# ESP32-SCHEMATIC.net
KiCad netlist of a schematic drawn in Altium Designer
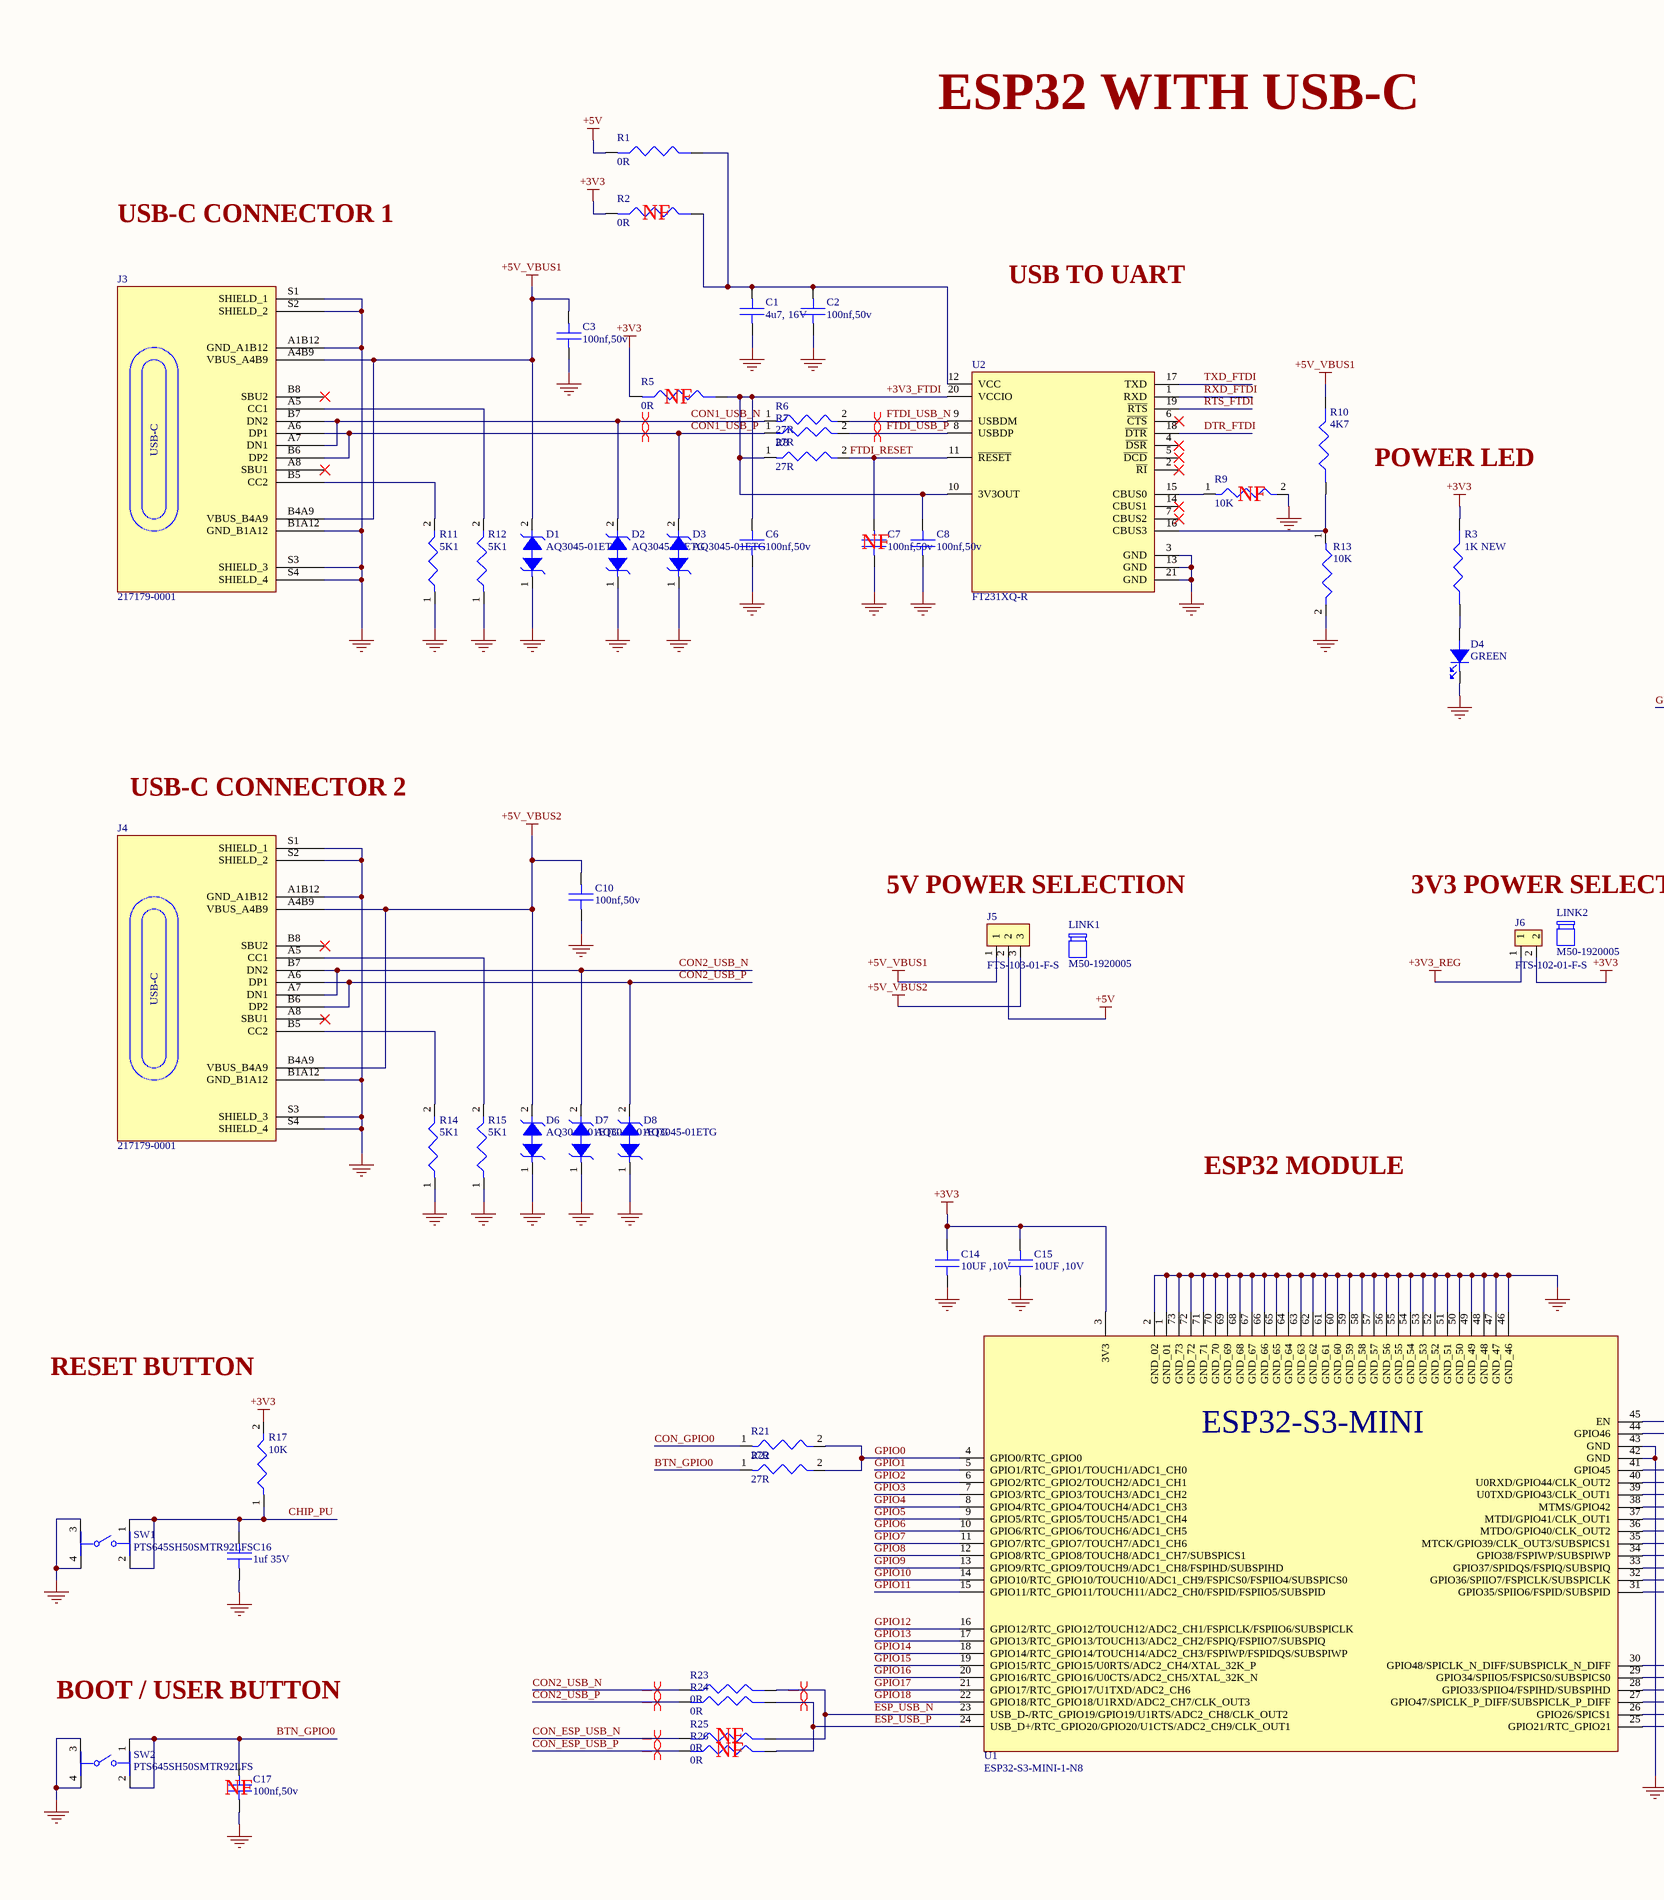
[diagram p0: ESP32-SCHEMATIC.SchDoc, left]
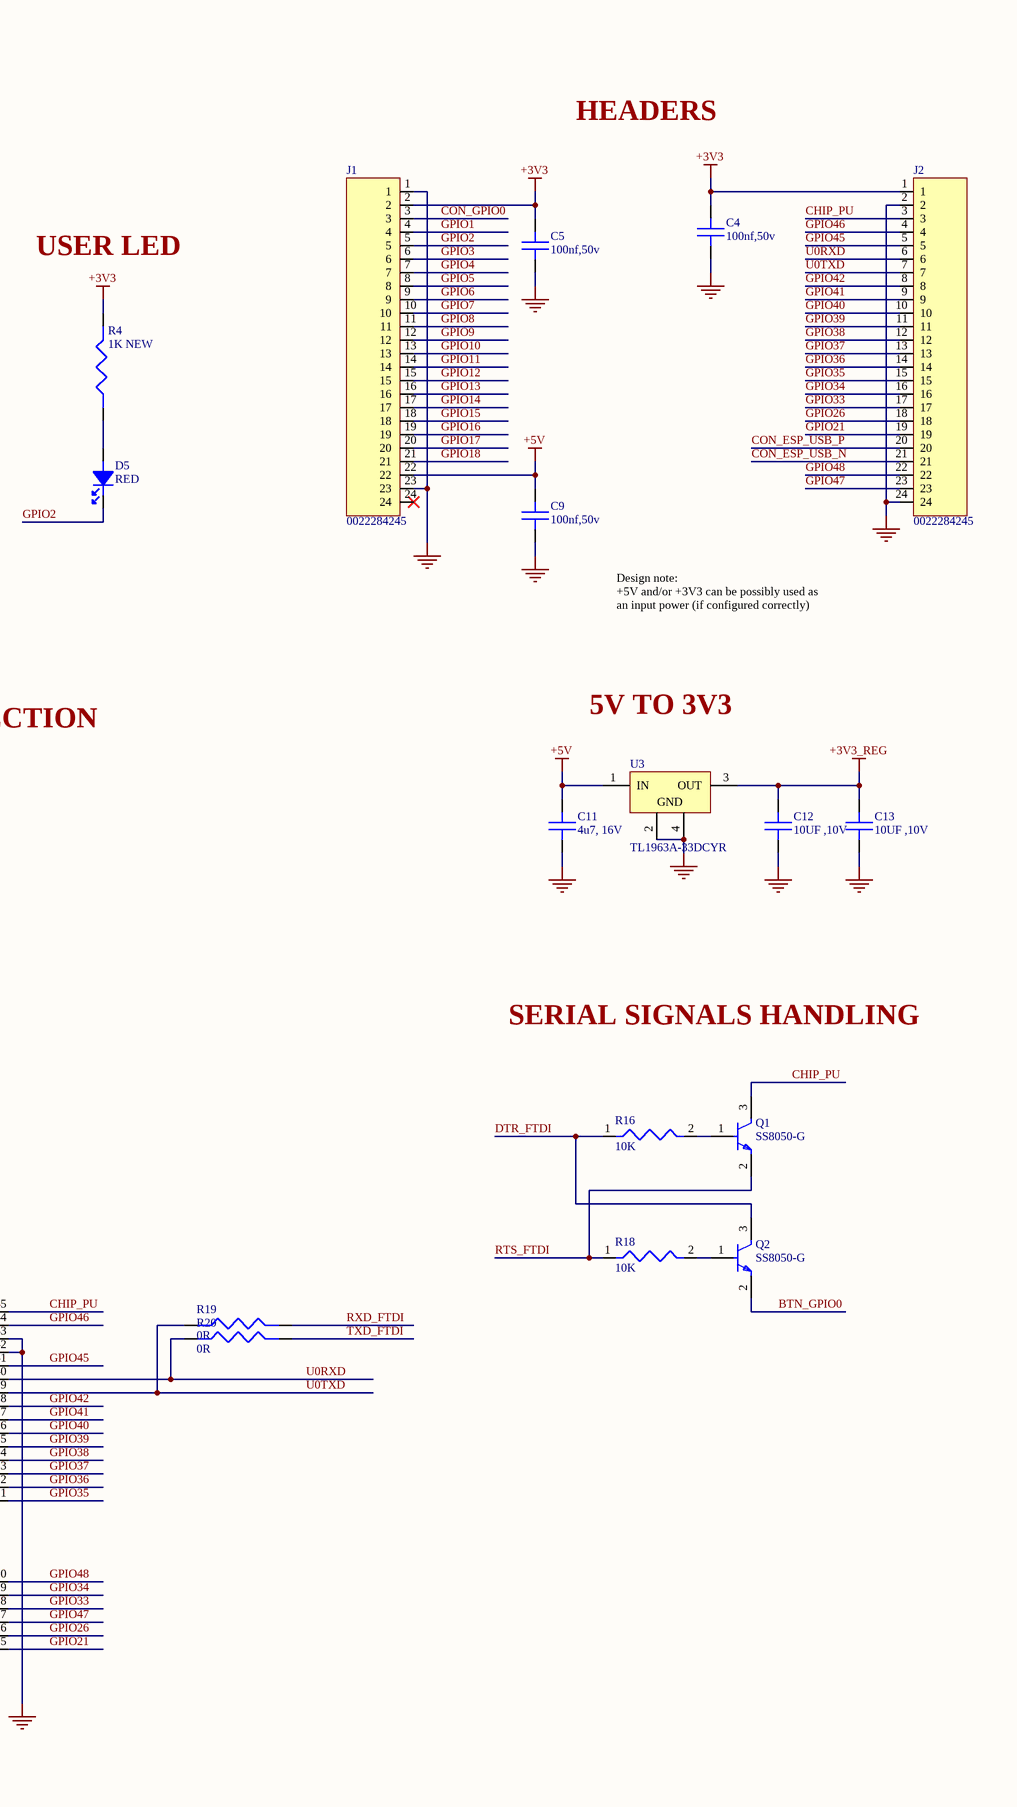
[diagram p1: ESP32-SCHEMATIC.SchDoc, right]

(export (version "E")
  (design (tool "Eeschema 10.0.6"))
  (components
    (comp (ref "C1")
      (value "4u7, 16V")
      (footprint "CAPC1005X55N")
      (description "16V 4.7uF X5R ±20% 0402 Multilayer Ceramic Capacitors MLCC - SMD/SMT ROHS")
      (fields
        (field (name "MANUFACTURER") "Samsung Electro-Mechanics")
        (field (name "MANUFACTURER PART NUMBER") "CL05A475MO5NUNC")
      )
      (libsource (lib "Schlib1") (part "CL05A475MO5NUNC"))
    )
    (comp (ref "C2")
      (value "100nf,50v")
      (footprint "CAPC1005X55N")
      (description "50V 100nF X7R ±10% 0402 Multilayer Ceramic Capacitors MLCC - SMD/SMT ROHS")
      (fields
        (field (name "MANUFACTURER") "Samsung Electro-Mechanics")
        (field (name "MANUFACTURER PART NUMBER") "CL05B104KB54PNC")
      )
      (libsource (lib "Schlib1") (part "CL05B104KB54PNC"))
    )
    (comp (ref "C3")
      (value "100nf,50v")
      (footprint "CAPC1005X55N")
      (description "50V 100nF X7R ±10% 0402 Multilayer Ceramic Capacitors MLCC - SMD/SMT ROHS")
      (fields
        (field (name "MANUFACTURER") "Samsung Electro-Mechanics")
        (field (name "MANUFACTURER PART NUMBER") "CL05B104KB54PNC")
      )
      (libsource (lib "Schlib1") (part "CL05B104KB54PNC"))
    )
    (comp (ref "C4")
      (value "100nf,50v")
      (footprint "CAPC1005X55N")
      (description "50V 100nF X7R ±10% 0402 Multilayer Ceramic Capacitors MLCC - SMD/SMT ROHS")
      (fields
        (field (name "MANUFACTURER") "Samsung Electro-Mechanics")
        (field (name "MANUFACTURER PART NUMBER") "CL05B104KB54PNC")
      )
      (libsource (lib "Schlib1") (part "CL05B104KB54PNC"))
    )
    (comp (ref "C5")
      (value "100nf,50v")
      (footprint "CAPC1005X55N")
      (description "50V 100nF X7R ±10% 0402 Multilayer Ceramic Capacitors MLCC - SMD/SMT ROHS")
      (fields
        (field (name "MANUFACTURER") "Samsung Electro-Mechanics")
        (field (name "MANUFACTURER PART NUMBER") "CL05B104KB54PNC")
      )
      (libsource (lib "Schlib1") (part "CL05B104KB54PNC"))
    )
    (comp (ref "C6")
      (value "100nf,50v")
      (footprint "CAPC1005X55N")
      (description "50V 100nF X7R ±10% 0402 Multilayer Ceramic Capacitors MLCC - SMD/SMT ROHS")
      (fields
        (field (name "MANUFACTURER") "Samsung Electro-Mechanics")
        (field (name "MANUFACTURER PART NUMBER") "CL05B104KB54PNC")
      )
      (libsource (lib "Schlib1") (part "CL05B104KB54PNC"))
    )
    (comp (ref "C7")
      (value "100nf,50v")
      (footprint "CAPC1005X55N")
      (description "50V 100nF X7R ±10% 0402 Multilayer Ceramic Capacitors MLCC - SMD/SMT ROHS")
      (fields
        (field (name "MANUFACTURER") "Samsung Electro-Mechanics")
        (field (name "MANUFACTURER PART NUMBER") "CL05B104KB54PNC")
      )
      (libsource (lib "Schlib1") (part "CL05B104KB54PNC"))
    )
    (comp (ref "C8")
      (value "100nf,50v")
      (footprint "CAPC1005X55N")
      (description "50V 100nF X7R ±10% 0402 Multilayer Ceramic Capacitors MLCC - SMD/SMT ROHS")
      (fields
        (field (name "MANUFACTURER") "Samsung Electro-Mechanics")
        (field (name "MANUFACTURER PART NUMBER") "CL05B104KB54PNC")
      )
      (libsource (lib "Schlib1") (part "CL05B104KB54PNC"))
    )
    (comp (ref "C9")
      (value "100nf,50v")
      (footprint "CAPC1005X55N")
      (description "50V 100nF X7R ±10% 0402 Multilayer Ceramic Capacitors MLCC - SMD/SMT ROHS")
      (fields
        (field (name "MANUFACTURER") "Samsung Electro-Mechanics")
        (field (name "MANUFACTURER PART NUMBER") "CL05B104KB54PNC")
      )
      (libsource (lib "Schlib1") (part "CL05B104KB54PNC"))
    )
    (comp (ref "C10")
      (value "100nf,50v")
      (footprint "CAPC1005X55N")
      (description "50V 100nF X7R ±10% 0402 Multilayer Ceramic Capacitors MLCC - SMD/SMT ROHS")
      (fields
        (field (name "MANUFACTURER") "Samsung Electro-Mechanics")
        (field (name "MANUFACTURER PART NUMBER") "CL05B104KB54PNC")
      )
      (libsource (lib "Schlib1") (part "CL05B104KB54PNC"))
    )
    (comp (ref "C11")
      (value "4u7, 16V")
      (footprint "CAPC1005X55N")
      (description "16V 4.7uF X5R ±20% 0402 Multilayer Ceramic Capacitors MLCC - SMD/SMT ROHS")
      (fields
        (field (name "MANUFACTURER") "Samsung Electro-Mechanics")
        (field (name "MANUFACTURER PART NUMBER") "CL05A475MO5NUNC")
      )
      (libsource (lib "Schlib1") (part "CL05A475MO5NUNC"))
    )
    (comp (ref "C12")
      (value "10UF ,10V")
      (footprint "CAPC1005X55N")
      (fields
        (field (name "MANUFACTURER") "Samsung Electro-Mechanics")
        (field (name "MANUFACTURER PART NUMBER") "CL05A106MP8NUB8")
        (field (name "TOLERANCE") "20%")
      )
      (libsource (lib "Schlib1") (part "CL05A106MP8NUB8"))
    )
    (comp (ref "C13")
      (value "10UF ,10V")
      (footprint "CAPC1005X55N")
      (fields
        (field (name "MANUFACTURER") "Samsung Electro-Mechanics")
        (field (name "MANUFACTURER PART NUMBER") "CL05A106MP8NUB8")
        (field (name "TOLERANCE") "20%")
      )
      (libsource (lib "Schlib1") (part "CL05A106MP8NUB8"))
    )
    (comp (ref "C14")
      (value "10UF ,10V")
      (footprint "CAPC1005X55N")
      (fields
        (field (name "MANUFACTURER") "Samsung Electro-Mechanics")
        (field (name "MANUFACTURER PART NUMBER") "CL05A106MP8NUB8")
        (field (name "TOLERANCE") "20%")
      )
      (libsource (lib "Schlib1") (part "CL05A106MP8NUB8"))
    )
    (comp (ref "C15")
      (value "10UF ,10V")
      (footprint "CAPC1005X55N")
      (fields
        (field (name "MANUFACTURER") "Samsung Electro-Mechanics")
        (field (name "MANUFACTURER PART NUMBER") "CL05A106MP8NUB8")
        (field (name "TOLERANCE") "20%")
      )
      (libsource (lib "Schlib1") (part "CL05A106MP8NUB8"))
    )
    (comp (ref "C16")
      (value "1uf 35V")
      (footprint "CAPC1005X55N")
      (description "35V 1uF X5R ±10% 0402 Multilayer Ceramic Capacitors MLCC - SMD/SMT ROHS")
      (fields
        (field (name "MANUFACTURER") "Samsung Electro-Mechanics")
        (field (name "MANUFACTURER PART NUMBER") "CL05A105KL5NRNC")
      )
      (libsource (lib "Schlib1") (part "CL05A105KL5NRNC"))
    )
    (comp (ref "C17")
      (value "100nf,50v")
      (footprint "CAPC1005X55N")
      (description "50V 100nF X7R ±10% 0402 Multilayer Ceramic Capacitors MLCC - SMD/SMT ROHS")
      (fields
        (field (name "MANUFACTURER") "Samsung Electro-Mechanics")
        (field (name "MANUFACTURER PART NUMBER") "CL05B104KB54PNC")
      )
      (libsource (lib "Schlib1") (part "CL05B104KB54PNC"))
    )
    (comp (ref "D1")
      (value "AQ3045-01ETG")
      (footprint "SOD882")
      (description "Bi 30Kv 5V 0.35Pf Automotve Tvs Sod882/ Tr Rohs Compliant: Yes ¦Littelfuse AQ3045-01ETG")
      (fields (field (name "MANUFACTURER") "Littelfuse"))
      (libsource (lib "Schlib1") (part "AQ3045-01ETG"))
    )
    (comp (ref "D2")
      (value "AQ3045-01ETG")
      (footprint "SOD882")
      (description "Bi 30Kv 5V 0.35Pf Automotve Tvs Sod882/ Tr Rohs Compliant: Yes ¦Littelfuse AQ3045-01ETG")
      (fields (field (name "MANUFACTURER") "Littelfuse"))
      (libsource (lib "Schlib1") (part "AQ3045-01ETG"))
    )
    (comp (ref "D3")
      (value "AQ3045-01ETG")
      (footprint "SOD882")
      (description "Bi 30Kv 5V 0.35Pf Automotve Tvs Sod882/ Tr Rohs Compliant: Yes ¦Littelfuse AQ3045-01ETG")
      (fields (field (name "MANUFACTURER") "Littelfuse"))
      (libsource (lib "Schlib1") (part "AQ3045-01ETG"))
    )
    (comp (ref "D4")
      (value "GREEN")
      (footprint "LED0402G")
      (description "LED Uni-Color Green 574nm 2-Pin Chip 0402(1006Metric) T/R")
      (fields
        (field (name "MANUFACTURER") "Vishay")
        (field (name "MANUFACTURER PART NUMBER") "VLMG1500-GS08")
      )
      (libsource (lib "Schlib1") (part "VLMG1500-GS08"))
    )
    (comp (ref "D5")
      (value "RED")
      (footprint "LED0402R")
      (description "LED Uni-Color Super Red 639nm 2-Pin Chip 0402(1006Metric) T/R")
      (fields
        (field (name "MANUFACTURER") "Vishay")
        (field (name "MANUFACTURER PART NUMBER") "VLMS1500-GS08")
      )
      (libsource (lib "Schlib1") (part "VLMS1500-GS08"))
    )
    (comp (ref "D6")
      (value "AQ3045-01ETG")
      (footprint "SOD882")
      (description "Bi 30Kv 5V 0.35Pf Automotve Tvs Sod882/ Tr Rohs Compliant: Yes ¦Littelfuse AQ3045-01ETG")
      (fields (field (name "MANUFACTURER") "Littelfuse"))
      (libsource (lib "Schlib1") (part "AQ3045-01ETG"))
    )
    (comp (ref "D7")
      (value "AQ3045-01ETG")
      (footprint "SOD882")
      (description "Bi 30Kv 5V 0.35Pf Automotve Tvs Sod882/ Tr Rohs Compliant: Yes ¦Littelfuse AQ3045-01ETG")
      (fields (field (name "MANUFACTURER") "Littelfuse"))
      (libsource (lib "Schlib1") (part "AQ3045-01ETG"))
    )
    (comp (ref "D8")
      (value "AQ3045-01ETG")
      (footprint "SOD882")
      (description "Bi 30Kv 5V 0.35Pf Automotve Tvs Sod882/ Tr Rohs Compliant: Yes ¦Littelfuse AQ3045-01ETG")
      (fields (field (name "MANUFACTURER") "Littelfuse"))
      (libsource (lib "Schlib1") (part "AQ3045-01ETG"))
    )
    (comp (ref "J1")
      (value "0022284245")
      (footprint "HDR_1X24_2.54MM")
      (description "Conn Unshrouded Header HDR 24 POS 2.54mm Solder ST Thru-Hole KK® Bag")
      (fields (field (name "MANUFACTURER") "Molex") (field (name "MANUFACTURER PART NUMBER") "22-28-4245"))
      (libsource (lib "") (part "22-28-4245_1"))
    )
    (comp (ref "J2")
      (value "0022284245")
      (footprint "HDR_1X24_2.54MM")
      (description "Conn Unshrouded Header HDR 24 POS 2.54mm Solder ST Thru-Hole KK® Bag")
      (fields (field (name "MANUFACTURER") "Molex") (field (name "MANUFACTURER PART NUMBER") "22-28-4245"))
      (libsource (lib "Schlib1") (part "22-28-4245"))
    )
    (comp (ref "J3")
      (value "217179-0001")
      (footprint "FP-2171790001-MFG")
      (description "USB Connector, USB Type C, USB 2.0, Receptacle, 16 Ways, Surface Mount, Through Hole Mount")
      (fields (field (name "MANUFACTURER") "Molex"))
      (libsource (lib "Schlib1") (part "217179-0001"))
    )
    (comp (ref "J4")
      (value "217179-0001")
      (footprint "FP-2171790001-MFG")
      (description "USB Connector, USB Type C, USB 2.0, Receptacle, 16 Ways, Surface Mount, Through Hole Mount")
      (fields (field (name "MANUFACTURER") "Molex"))
      (libsource (lib "Schlib1") (part "217179-0001"))
    )
    (comp (ref "J5")
      (value "FTS-103-01-F-S")
      (footprint "HDR_1X3_1.27MM")
      (description "Pin Header, Wire-to-Board, 1.27 mm, 1 Rows, 3 Contacts, Through Hole, FTS")
      (fields (field (name "MANUFACTURER") "Samtec"))
      (libsource (lib "Schlib1") (part "FTS-103-01-F-S"))
    )
    (comp (ref "J6")
      (value "FTS-102-01-F-S")
      (footprint "HDR_1X2_1.27MM")
      (description "Pin Header, Board-to-Board, 1.27 mm, 1 Rows, 2 Contacts, Through Hole Straight, FTS Series")
      (fields (field (name "MANUFACTURER") "Samtec"))
      (libsource (lib "Schlib1") (part "FTS-102-01-F-S"))
    )
    (comp (ref "LINK1")
      (value "M50-1920005")
      (description "1.27mm (0.05) Pitch Closed Top Jumper Socket, red, gold\"")
      (fields (field (name "MANUFACTURER") "Harwin"))
      (libsource (lib "Schlib1") (part "M50-1920005"))
    )
    (comp (ref "LINK2")
      (value "M50-1920005")
      (description "1.27mm (0.05) Pitch Closed Top Jumper Socket, red, gold\"")
      (fields (field (name "MANUFACTURER") "Harwin"))
      (libsource (lib "Schlib1") (part "M50-1920005"))
    )
    (comp (ref "Q1")
      (value "SS8050-G")
      (footprint "FP-SS8050-G-IPC_B")
      (description "Trans Gp Bjt NPN 25V 1.5A 300MW 3-PIN SOT-23 T/r")
      (fields (field (name "MANUFACTURER") "Comchip"))
      (libsource (lib "Schlib1") (part "SS8050-G"))
    )
    (comp (ref "Q2")
      (value "SS8050-G")
      (footprint "FP-SS8050-G-IPC_B")
      (description "Trans Gp Bjt NPN 25V 1.5A 300MW 3-PIN SOT-23 T/r")
      (fields (field (name "MANUFACTURER") "Comchip"))
      (libsource (lib "Schlib1") (part "SS8050-G"))
    )
    (comp (ref "R1")
      (value "0R")
      (footprint "RESC1005X37N")
      (description "GENERAL PURPOSE CHIP RESISTOR Metal Glaze/thick Film, 0.0625W, 0ohm, Surface Mount, 0402")
      (fields
        (field (name "MANUFACTURER") "Yageo Group")
        (field (name "MANUFACTURER PART NUMBER") "RC0402JR-070RL")
      )
      (libsource (lib "Schlib1") (part "RC0402JR-070RL"))
    )
    (comp (ref "R2")
      (value "0R")
      (footprint "RESC1005X37N")
      (description "GENERAL PURPOSE CHIP RESISTOR Metal Glaze/thick Film, 0.0625W, 0ohm, Surface Mount, 0402")
      (fields
        (field (name "MANUFACTURER") "Yageo Group")
        (field (name "MANUFACTURER PART NUMBER") "RC0402JR-070RL")
      )
      (libsource (lib "Schlib1") (part "RC0402JR-070RL"))
    )
    (comp (ref "R3")
      (value "1K NEW")
      (footprint "RESC1005X37N")
      (description "Resistor, thick film, SMD 0402 (1005), 1 kΩ, 0.063 W, ±1 %, RC0402FR-071KL")
      (fields
        (field (name "MANUFACTURER") "Yageo Group")
        (field (name "MANUFACTURER PART NUMBER") "RC0402FR-071KL")
      )
      (libsource (lib "Schlib1") (part "RC0402FR-071KL"))
    )
    (comp (ref "R4")
      (value "1K NEW")
      (footprint "RESC1005X37N")
      (description "Resistor, thick film, SMD 0402 (1005), 1 kΩ, 0.063 W, ±1 %, RC0402FR-071KL")
      (fields
        (field (name "MANUFACTURER") "Yageo Group")
        (field (name "MANUFACTURER PART NUMBER") "RC0402FR-071KL")
      )
      (libsource (lib "Schlib1") (part "RC0402FR-071KL"))
    )
    (comp (ref "R5")
      (value "0R")
      (footprint "RESC1005X37N")
      (description "GENERAL PURPOSE CHIP RESISTOR Metal Glaze/thick Film, 0.0625W, 0ohm, Surface Mount, 0402")
      (fields
        (field (name "MANUFACTURER") "Yageo Group")
        (field (name "MANUFACTURER PART NUMBER") "RC0402JR-070RL")
      )
      (libsource (lib "Schlib1") (part "RC0402JR-070RL"))
    )
    (comp (ref "R6")
      (value "27R")
      (footprint "RESC1005X37N")
      (description "62.5mW Thick Film Resistors 50V ±100ppm/℃ ±1% 27Ω 0402 Chip Resistor - Surface Mount ROHS")
      (fields
        (field (name "MANUFACTURER") "Yageo Group")
        (field (name "MANUFACTURER PART NUMBER") "RC0402FR-0727RL")
      )
      (libsource (lib "Schlib1") (part "RC0402FR-0727RL"))
    )
    (comp (ref "R7")
      (value "27R")
      (footprint "RESC1005X37N")
      (description "62.5mW Thick Film Resistors 50V ±100ppm/℃ ±1% 27Ω 0402 Chip Resistor - Surface Mount ROHS")
      (fields
        (field (name "MANUFACTURER") "Yageo Group")
        (field (name "MANUFACTURER PART NUMBER") "RC0402FR-0727RL")
      )
      (libsource (lib "Schlib1") (part "RC0402FR-0727RL"))
    )
    (comp (ref "R8")
      (value "27R")
      (footprint "RESC1005X37N")
      (description "62.5mW Thick Film Resistors 50V ±100ppm/℃ ±1% 27Ω 0402 Chip Resistor - Surface Mount ROHS")
      (fields
        (field (name "MANUFACTURER") "Yageo Group")
        (field (name "MANUFACTURER PART NUMBER") "RC0402FR-0727RL")
      )
      (libsource (lib "Schlib1") (part "RC0402FR-0727RL"))
    )
    (comp (ref "R9")
      (value "10K")
      (footprint "RESC1005X37N")
      (description "62.5mW Thick Film Resistors 50V ±100ppm/℃ ±1% 10kΩ 0402 Chip Resistor - Surface Mount ROHS")
      (fields
        (field (name "MANUFACTURER") "Yageo Group")
        (field (name "MANUFACTURER PART NUMBER") "SR0402FR-0710KL")
      )
      (libsource (lib "Schlib1") (part "SR0402FR-0710KL"))
    )
    (comp (ref "R10")
      (value "4K7")
      (footprint "RESC1005X37N")
      (description "Res General Purpose Thick Film 0402 4.7K Ohm 1% 1/16W ±100ppm/°C Molded SMD Paper T/R")
      (fields
        (field (name "MANUFACTURER") "Yageo Group")
        (field (name "MANUFACTURER PART NUMBER") "RC0402FR-074K7L")
      )
      (libsource (lib "Schlib1") (part "RC0402FR-074K7L"))
    )
    (comp (ref "R11")
      (value "5K1")
      (footprint "RESC1005X37N")
      (description "62.5mW Thick Film Resistors 50V ±100ppm/℃ ±1% 5.1kΩ 0402 Chip Resistor - Surface Mount ROHS")
      (fields
        (field (name "MANUFACTURER") "Yageo Group")
        (field (name "MANUFACTURER PART NUMBER") "AC0402FR-075K1L")
      )
      (libsource (lib "Schlib1") (part "AC0402FR-075K1L"))
    )
    (comp (ref "R12")
      (value "5K1")
      (footprint "RESC1005X37N")
      (description "62.5mW Thick Film Resistors 50V ±100ppm/℃ ±1% 5.1kΩ 0402 Chip Resistor - Surface Mount ROHS")
      (fields
        (field (name "MANUFACTURER") "Yageo Group")
        (field (name "MANUFACTURER PART NUMBER") "AC0402FR-075K1L")
      )
      (libsource (lib "Schlib1") (part "AC0402FR-075K1L"))
    )
    (comp (ref "R13")
      (value "10K")
      (footprint "RESC1005X37N")
      (description "62.5mW Thick Film Resistors 50V ±100ppm/℃ ±1% 10kΩ 0402 Chip Resistor - Surface Mount ROHS")
      (fields
        (field (name "MANUFACTURER") "Yageo Group")
        (field (name "MANUFACTURER PART NUMBER") "SR0402FR-0710KL")
      )
      (libsource (lib "Schlib1") (part "SR0402FR-0710KL"))
    )
    (comp (ref "R14")
      (value "5K1")
      (footprint "RESC1005X37N")
      (description "62.5mW Thick Film Resistors 50V ±100ppm/℃ ±1% 5.1kΩ 0402 Chip Resistor - Surface Mount ROHS")
      (fields
        (field (name "MANUFACTURER") "Yageo Group")
        (field (name "MANUFACTURER PART NUMBER") "AC0402FR-075K1L")
      )
      (libsource (lib "Schlib1") (part "AC0402FR-075K1L"))
    )
    (comp (ref "R15")
      (value "5K1")
      (footprint "RESC1005X37N")
      (description "62.5mW Thick Film Resistors 50V ±100ppm/℃ ±1% 5.1kΩ 0402 Chip Resistor - Surface Mount ROHS")
      (fields
        (field (name "MANUFACTURER") "Yageo Group")
        (field (name "MANUFACTURER PART NUMBER") "AC0402FR-075K1L")
      )
      (libsource (lib "Schlib1") (part "AC0402FR-075K1L"))
    )
    (comp (ref "R16")
      (value "10K")
      (footprint "RESC1005X37N")
      (description "62.5mW Thick Film Resistors 50V ±100ppm/℃ ±1% 10kΩ 0402 Chip Resistor - Surface Mount ROHS")
      (fields
        (field (name "MANUFACTURER") "Yageo Group")
        (field (name "MANUFACTURER PART NUMBER") "SR0402FR-0710KL")
      )
      (libsource (lib "Schlib1") (part "SR0402FR-0710KL"))
    )
    (comp (ref "R17")
      (value "10K")
      (footprint "RESC1005X37N")
      (description "62.5mW Thick Film Resistors 50V ±100ppm/℃ ±1% 10kΩ 0402 Chip Resistor - Surface Mount ROHS")
      (fields
        (field (name "MANUFACTURER") "Yageo Group")
        (field (name "MANUFACTURER PART NUMBER") "SR0402FR-0710KL")
      )
      (libsource (lib "Schlib1") (part "SR0402FR-0710KL"))
    )
    (comp (ref "R18")
      (value "10K")
      (footprint "RESC1005X37N")
      (description "62.5mW Thick Film Resistors 50V ±100ppm/℃ ±1% 10kΩ 0402 Chip Resistor - Surface Mount ROHS")
      (fields
        (field (name "MANUFACTURER") "Yageo Group")
        (field (name "MANUFACTURER PART NUMBER") "SR0402FR-0710KL")
      )
      (libsource (lib "Schlib1") (part "SR0402FR-0710KL"))
    )
    (comp (ref "R19")
      (value "0R")
      (footprint "RESC1005X37N")
      (description "GENERAL PURPOSE CHIP RESISTOR Metal Glaze/thick Film, 0.0625W, 0ohm, Surface Mount, 0402")
      (fields
        (field (name "MANUFACTURER") "Yageo Group")
        (field (name "MANUFACTURER PART NUMBER") "RC0402JR-070RL")
      )
      (libsource (lib "Schlib1") (part "RC0402JR-070RL"))
    )
    (comp (ref "R20")
      (value "0R")
      (footprint "RESC1005X37N")
      (description "GENERAL PURPOSE CHIP RESISTOR Metal Glaze/thick Film, 0.0625W, 0ohm, Surface Mount, 0402")
      (fields
        (field (name "MANUFACTURER") "Yageo Group")
        (field (name "MANUFACTURER PART NUMBER") "RC0402JR-070RL")
      )
      (libsource (lib "Schlib1") (part "RC0402JR-070RL"))
    )
    (comp (ref "R21")
      (value "27R")
      (footprint "RESC1005X37N")
      (description "62.5mW Thick Film Resistors 50V ±100ppm/℃ ±1% 27Ω 0402 Chip Resistor - Surface Mount ROHS")
      (fields
        (field (name "MANUFACTURER") "Yageo Group")
        (field (name "MANUFACTURER PART NUMBER") "RC0402FR-0727RL")
      )
      (libsource (lib "Schlib1") (part "RC0402FR-0727RL"))
    )
    (comp (ref "R22")
      (value "27R")
      (footprint "RESC1005X37N")
      (description "62.5mW Thick Film Resistors 50V ±100ppm/℃ ±1% 27Ω 0402 Chip Resistor - Surface Mount ROHS")
      (fields
        (field (name "MANUFACTURER") "Yageo Group")
        (field (name "MANUFACTURER PART NUMBER") "RC0402FR-0727RL")
      )
      (libsource (lib "Schlib1") (part "RC0402FR-0727RL"))
    )
    (comp (ref "R23")
      (value "0R")
      (footprint "RESC1005X37N")
      (description "GENERAL PURPOSE CHIP RESISTOR Metal Glaze/thick Film, 0.0625W, 0ohm, Surface Mount, 0402")
      (fields
        (field (name "MANUFACTURER") "Yageo Group")
        (field (name "MANUFACTURER PART NUMBER") "RC0402JR-070RL")
      )
      (libsource (lib "Schlib1") (part "RC0402JR-070RL"))
    )
    (comp (ref "R24")
      (value "0R")
      (footprint "RESC1005X37N")
      (description "GENERAL PURPOSE CHIP RESISTOR Metal Glaze/thick Film, 0.0625W, 0ohm, Surface Mount, 0402")
      (fields
        (field (name "MANUFACTURER") "Yageo Group")
        (field (name "MANUFACTURER PART NUMBER") "RC0402JR-070RL")
      )
      (libsource (lib "Schlib1") (part "RC0402JR-070RL"))
    )
    (comp (ref "R25")
      (value "0R")
      (footprint "RESC1005X37N")
      (description "GENERAL PURPOSE CHIP RESISTOR Metal Glaze/thick Film, 0.0625W, 0ohm, Surface Mount, 0402")
      (fields
        (field (name "MANUFACTURER") "Yageo Group")
        (field (name "MANUFACTURER PART NUMBER") "RC0402JR-070RL")
      )
      (libsource (lib "Schlib1") (part "RC0402JR-070RL"))
    )
    (comp (ref "R26")
      (value "0R")
      (footprint "RESC1005X37N")
      (description "GENERAL PURPOSE CHIP RESISTOR Metal Glaze/thick Film, 0.0625W, 0ohm, Surface Mount, 0402")
      (fields
        (field (name "MANUFACTURER") "Yageo Group")
        (field (name "MANUFACTURER PART NUMBER") "RC0402JR-070RL")
      )
      (libsource (lib "Schlib1") (part "RC0402JR-070RL"))
    )
    (comp (ref "SW1")
      (value "PTS645SH50SMTR92LFS")
      (footprint "FP-PTS645SH50SMTR92LFS-MFG")
      (description "Switch Tactile N.O. SPST Round Button Gull Wing 0.05A 12VDC 100000Cycles 1.96N SMD T/R")
      (fields (field (name "MANUFACTURER") "C&K Components"))
      (libsource (lib "Schlib1") (part "PTS645SH50SMTR92LFS"))
    )
    (comp (ref "SW2")
      (value "PTS645SH50SMTR92LFS")
      (footprint "FP-PTS645SH50SMTR92LFS-MFG")
      (description "Switch Tactile N.O. SPST Round Button Gull Wing 0.05A 12VDC 100000Cycles 1.96N SMD T/R")
      (fields (field (name "MANUFACTURER") "C&K Components"))
      (libsource (lib "Schlib1") (part "PTS645SH50SMTR92LFS"))
    )
    (comp (ref "U1")
      (value "ESP32-S3-MINI-1-N8")
      (footprint "XCVR_ESP32-S3-MINI-1-N8")
      (description "SMD module, ESP32-S3FN8, 8 MB SPI flash, PCB antenna")
      (fields (field (name "MANUFACTURER") "Espressif Systems"))
      (libsource (lib "Schlib1") (part "ESP32-S3-MINI-1-N8"))
    )
    (comp (ref "U2")
      (value "FT231XQ-R")
      (footprint "FP-QFN-20-IPC_B")
      (description "Tape & Reel (TR) 2006 UART USB 2.0 interface controller 3.3V~5V 4mm 8mA 12Mbps")
      (fields (field (name "MANUFACTURER") "FTDI"))
      (libsource (lib "Schlib1") (part "FT231XQ-R"))
    )
    (comp (ref "U3")
      (value "TL1963A-33DCYR")
      (footprint "DCY0004A_N")
      (description "1.5-A, 20-V, low-dropout voltage regulator with reverse current & reverse voltage protection")
      (fields (field (name "MANUFACTURER") "Texas Instruments"))
      (libsource (lib "Schlib1") (part "TL1963A-33DCYR"))
    )
  )
  (nets
    (net (code "1") (name "+3V3") (class "Default")
      (node (ref "C14") (pin "2") (pinfunction "2_2") (pintype "passive"))
      (node (ref "C15") (pin "2") (pinfunction "2_2") (pintype "passive"))
      (node (ref "C4") (pin "2") (pinfunction "2_2") (pintype "passive"))
      (node (ref "C5") (pin "2") (pinfunction "2_2") (pintype "passive"))
      (node (ref "J1") (pin "2") (pinfunction "2_2") (pintype "passive"))
      (node (ref "J2") (pin "1") (pinfunction "1_1") (pintype "passive"))
      (node (ref "J6") (pin "2") (pinfunction "2_2") (pintype "passive"))
      (node (ref "R17") (pin "2") (pinfunction "2_2") (pintype "passive"))
      (node (ref "R2") (pin "1") (pinfunction "1_1") (pintype "passive"))
      (node (ref "R3") (pin "2") (pinfunction "2_2") (pintype "passive"))
      (node (ref "R4") (pin "2") (pinfunction "2_2") (pintype "passive"))
      (node (ref "R5") (pin "1") (pinfunction "1_1") (pintype "passive"))
      (node (ref "U1") (pin "3") (pinfunction "3V3_3") (pintype "passive"))
    )
    (net (code "2") (name "+3V3_REG") (class "Default")
      (node (ref "C12") (pin "2") (pinfunction "2_2") (pintype "passive"))
      (node (ref "C13") (pin "2") (pinfunction "2_2") (pintype "passive"))
      (node (ref "J6") (pin "1") (pinfunction "1_1") (pintype "passive"))
      (node (ref "U3") (pin "3") (pinfunction "OUT_3") (pintype "power_in"))
    )
    (net (code "3") (name "+5V") (class "Default")
      (node (ref "C11") (pin "2") (pinfunction "2_2") (pintype "passive"))
      (node (ref "C9") (pin "2") (pinfunction "2_2") (pintype "passive"))
      (node (ref "J1") (pin "22") (pinfunction "22_22") (pintype "passive"))
      (node (ref "J5") (pin "2") (pinfunction "2_2") (pintype "passive"))
      (node (ref "R1") (pin "1") (pinfunction "1_1") (pintype "passive"))
      (node (ref "U3") (pin "1") (pinfunction "IN_1") (pintype "power_in"))
    )
    (net (code "4") (name "+5V_VBUS1") (class "Default")
      (node (ref "C3") (pin "2") (pinfunction "2_2") (pintype "passive"))
      (node (ref "D1") (pin "2") (pinfunction "2_2") (pintype "passive"))
      (node (ref "J3") (pin "A4B9") (pinfunction "VBUS_A4B9_A4B9") (pintype "passive"))
      (node (ref "J3") (pin "B4A9") (pinfunction "VBUS_B4A9_B4A9") (pintype "passive"))
      (node (ref "J5") (pin "1") (pinfunction "1_1") (pintype "passive"))
      (node (ref "R10") (pin "2") (pinfunction "2_2") (pintype "passive"))
    )
    (net (code "5") (name "+5V_VBUS2") (class "Default")
      (node (ref "C10") (pin "2") (pinfunction "2_2") (pintype "passive"))
      (node (ref "D6") (pin "2") (pinfunction "2_2") (pintype "passive"))
      (node (ref "J4") (pin "A4B9") (pinfunction "VBUS_A4B9_A4B9") (pintype "passive"))
      (node (ref "J4") (pin "B4A9") (pinfunction "VBUS_B4A9_B4A9") (pintype "passive"))
      (node (ref "J5") (pin "3") (pinfunction "3_3") (pintype "passive"))
    )
    (net (code "6") (name "/+3V3_FTDI") (class "Default")
      (node (ref "C6") (pin "2") (pinfunction "2_2") (pintype "passive"))
      (node (ref "C8") (pin "2") (pinfunction "2_2") (pintype "passive"))
      (node (ref "R5") (pin "2") (pinfunction "2_2") (pintype "passive"))
      (node (ref "R8") (pin "1") (pinfunction "1_1") (pintype "passive"))
      (node (ref "U2") (pin "10") (pinfunction "3V3OUT_10") (pintype "passive"))
      (node (ref "U2") (pin "20") (pinfunction "VCCIO_20") (pintype "passive"))
    )
    (net (code "7") (name "/BTN_GPIO0") (class "Default")
      (node (ref "C17") (pin "2") (pinfunction "2_2") (pintype "passive"))
      (node (ref "Q2") (pin "2") (pinfunction "E_2") (pintype "passive"))
      (node (ref "R22") (pin "1") (pinfunction "1_1") (pintype "passive"))
      (node (ref "SW2") (pin "1") (pinfunction "1_1") (pintype "passive"))
      (node (ref "SW2") (pin "2") (pinfunction "2_2") (pintype "passive"))
    )
    (net (code "8") (name "/CHIP_PU") (class "Default")
      (node (ref "C16") (pin "2") (pinfunction "2_2") (pintype "passive"))
      (node (ref "J2") (pin "3") (pinfunction "3_3") (pintype "passive"))
      (node (ref "Q1") (pin "3") (pinfunction "C_3") (pintype "passive"))
      (node (ref "R17") (pin "1") (pinfunction "1_1") (pintype "passive"))
      (node (ref "SW1") (pin "1") (pinfunction "1_1") (pintype "passive"))
      (node (ref "SW1") (pin "2") (pinfunction "2_2") (pintype "passive"))
      (node (ref "U1") (pin "45") (pinfunction "EN_45") (pintype "passive"))
    )
    (net (code "9") (name "/CON1_USB_N") (class "Default")
      (node (ref "D2") (pin "2") (pinfunction "2_2") (pintype "passive"))
      (node (ref "J3") (pin "A7") (pinfunction "DN1_A7") (pintype "passive"))
      (node (ref "J3") (pin "B7") (pinfunction "DN2_B7") (pintype "passive"))
      (node (ref "R6") (pin "1") (pinfunction "1_1") (pintype "passive"))
    )
    (net (code "10") (name "/CON1_USB_P") (class "Default")
      (node (ref "D3") (pin "2") (pinfunction "2_2") (pintype "passive"))
      (node (ref "J3") (pin "A6") (pinfunction "DP1_A6") (pintype "passive"))
      (node (ref "J3") (pin "B6") (pinfunction "DP2_B6") (pintype "passive"))
      (node (ref "R7") (pin "1") (pinfunction "1_1") (pintype "passive"))
    )
    (net (code "11") (name "/CON2_USB_N") (class "Default")
      (node (ref "D7") (pin "2") (pinfunction "2_2") (pintype "passive"))
      (node (ref "J4") (pin "A7") (pinfunction "DN1_A7") (pintype "passive"))
      (node (ref "J4") (pin "B7") (pinfunction "DN2_B7") (pintype "passive"))
      (node (ref "R23") (pin "1") (pinfunction "1_1") (pintype "passive"))
    )
    (net (code "12") (name "/CON2_USB_P") (class "Default")
      (node (ref "D8") (pin "2") (pinfunction "2_2") (pintype "passive"))
      (node (ref "J4") (pin "A6") (pinfunction "DP1_A6") (pintype "passive"))
      (node (ref "J4") (pin "B6") (pinfunction "DP2_B6") (pintype "passive"))
      (node (ref "R24") (pin "1") (pinfunction "1_1") (pintype "passive"))
    )
    (net (code "13") (name "/CON_ESP_USB_N") (class "Default")
      (node (ref "J2") (pin "21") (pinfunction "21_21") (pintype "passive"))
      (node (ref "R25") (pin "1") (pinfunction "1_1") (pintype "passive"))
    )
    (net (code "14") (name "/CON_ESP_USB_P") (class "Default")
      (node (ref "J2") (pin "20") (pinfunction "20_20") (pintype "passive"))
      (node (ref "R26") (pin "1") (pinfunction "1_1") (pintype "passive"))
    )
    (net (code "15") (name "/CON_GPIO0") (class "Default")
      (node (ref "J1") (pin "3") (pinfunction "3_3") (pintype "passive"))
      (node (ref "R21") (pin "1") (pinfunction "1_1") (pintype "passive"))
    )
    (net (code "16") (name "/DTR_FTDI") (class "Default")
      (node (ref "Q2") (pin "3") (pinfunction "C_3") (pintype "passive"))
      (node (ref "R16") (pin "1") (pinfunction "1_1") (pintype "passive"))
      (node (ref "U2") (pin "18") (pinfunction "~{DTR}_18") (pintype "passive"))
    )
    (net (code "17") (name "/ESP_USB_N") (class "Default")
      (node (ref "R23") (pin "2") (pinfunction "2_2") (pintype "passive"))
      (node (ref "R25") (pin "2") (pinfunction "2_2") (pintype "passive"))
      (node (ref "U1") (pin "23") (pinfunction "USB_D-/RTC_GPIO19/GPIO19/U1RTS/ADC2_CH8/CLK_OUT2_23") (pintype "passive"))
    )
    (net (code "18") (name "/ESP_USB_P") (class "Default")
      (node (ref "R24") (pin "2") (pinfunction "2_2") (pintype "passive"))
      (node (ref "R26") (pin "2") (pinfunction "2_2") (pintype "passive"))
      (node (ref "U1") (pin "24") (pinfunction "USB_D+/RTC_GPIO20/GPIO20/U1CTS/ADC2_CH9/CLK_OUT1_24") (pintype "passive"))
    )
    (net (code "19") (name "/FTDI_RESET") (class "Default")
      (node (ref "C7") (pin "2") (pinfunction "2_2") (pintype "passive"))
      (node (ref "R8") (pin "2") (pinfunction "2_2") (pintype "passive"))
      (node (ref "U2") (pin "11") (pinfunction "~{RESET}_11") (pintype "passive"))
    )
    (net (code "20") (name "/FTDI_USB_N") (class "Default")
      (node (ref "R6") (pin "2") (pinfunction "2_2") (pintype "passive"))
      (node (ref "U2") (pin "9") (pinfunction "USBDM_9") (pintype "passive"))
    )
    (net (code "21") (name "/FTDI_USB_P") (class "Default")
      (node (ref "R7") (pin "2") (pinfunction "2_2") (pintype "passive"))
      (node (ref "U2") (pin "8") (pinfunction "USBDP_8") (pintype "passive"))
    )
    (net (code "22") (name "/GPIO0") (class "Default")
      (node (ref "R21") (pin "2") (pinfunction "2_2") (pintype "passive"))
      (node (ref "R22") (pin "2") (pinfunction "2_2") (pintype "passive"))
      (node (ref "U1") (pin "4") (pinfunction "GPIO0/RTC_GPIO0_4") (pintype "passive"))
    )
    (net (code "23") (name "/GPIO1") (class "Default")
      (node (ref "J1") (pin "4") (pinfunction "4_4") (pintype "passive"))
      (node (ref "U1") (pin "5") (pinfunction "GPIO1/RTC_GPIO1/TOUCH1/ADC1_CH0_5") (pintype "passive"))
    )
    (net (code "24") (name "/GPIO2") (class "Default")
      (node (ref "D5") (pin "1") (pinfunction "1_1") (pintype "passive"))
      (node (ref "J1") (pin "5") (pinfunction "5_5") (pintype "passive"))
      (node (ref "U1") (pin "6") (pinfunction "GPIO2/RTC_GPIO2/TOUCH2/ADC1_CH1_6") (pintype "passive"))
    )
    (net (code "25") (name "/GPIO3") (class "Default")
      (node (ref "J1") (pin "6") (pinfunction "6_6") (pintype "passive"))
      (node (ref "U1") (pin "7") (pinfunction "GPIO3/RTC_GPIO3/TOUCH3/ADC1_CH2_7") (pintype "passive"))
    )
    (net (code "26") (name "/GPIO4") (class "Default")
      (node (ref "J1") (pin "7") (pinfunction "7_7") (pintype "passive"))
      (node (ref "U1") (pin "8") (pinfunction "GPIO4/RTC_GPIO4/TOUCH4/ADC1_CH3_8") (pintype "passive"))
    )
    (net (code "27") (name "/GPIO5") (class "Default")
      (node (ref "J1") (pin "8") (pinfunction "8_8") (pintype "passive"))
      (node (ref "U1") (pin "9") (pinfunction "GPIO5/RTC_GPIO5/TOUCH5/ADC1_CH4_9") (pintype "passive"))
    )
    (net (code "28") (name "/GPIO6") (class "Default")
      (node (ref "J1") (pin "9") (pinfunction "9_9") (pintype "passive"))
      (node (ref "U1") (pin "10") (pinfunction "GPIO6/RTC_GPIO6/TOUCH6/ADC1_CH5_10") (pintype "passive"))
    )
    (net (code "29") (name "/GPIO7") (class "Default")
      (node (ref "J1") (pin "10") (pinfunction "10_10") (pintype "passive"))
      (node (ref "U1") (pin "11") (pinfunction "GPIO7/RTC_GPIO7/TOUCH7/ADC1_CH6_11") (pintype "passive"))
    )
    (net (code "30") (name "/GPIO8") (class "Default")
      (node (ref "J1") (pin "11") (pinfunction "11_11") (pintype "passive"))
      (node (ref "U1") (pin "12") (pinfunction "GPIO8/RTC_GPIO8/TOUCH8/ADC1_CH7/SUBSPICS1_12") (pintype "passive"))
    )
    (net (code "31") (name "/GPIO9") (class "Default")
      (node (ref "J1") (pin "12") (pinfunction "12_12") (pintype "passive"))
      (node (ref "U1") (pin "13") (pinfunction "GPIO9/RTC_GPIO9/TOUCH9/ADC1_CH8/FSPIHD/SUBSPIHD_13") (pintype "passive"))
    )
    (net (code "32") (name "/GPIO10") (class "Default")
      (node (ref "J1") (pin "13") (pinfunction "13_13") (pintype "passive"))
      (node (ref "U1") (pin "14") (pinfunction "GPIO10/RTC_GPIO10/TOUCH10/ADC1_CH9/FSPICS0/FSPIIO4/SUBSPICS0_14") (pintype "passive"))
    )
    (net (code "33") (name "/GPIO11") (class "Default")
      (node (ref "J1") (pin "14") (pinfunction "14_14") (pintype "passive"))
      (node (ref "U1") (pin "15") (pinfunction "GPIO11/RTC_GPIO11/TOUCH11/ADC2_CH0/FSPID/FSPIIO5/SUBSPID_15") (pintype "passive"))
    )
    (net (code "34") (name "/GPIO12") (class "Default")
      (node (ref "J1") (pin "15") (pinfunction "15_15") (pintype "passive"))
      (node (ref "U1") (pin "16") (pinfunction "GPIO12/RTC_GPIO12/TOUCH12/ADC2_CH1/FSPICLK/FSPIIO6/SUBSPICLK_16") (pintype "passive"))
    )
    (net (code "35") (name "/GPIO13") (class "Default")
      (node (ref "J1") (pin "16") (pinfunction "16_16") (pintype "passive"))
      (node (ref "U1") (pin "17") (pinfunction "GPIO13/RTC_GPIO13/TOUCH13/ADC2_CH2/FSPIQ/FSPIIO7/SUBSPIQ_17") (pintype "passive"))
    )
    (net (code "36") (name "/GPIO14") (class "Default")
      (node (ref "J1") (pin "17") (pinfunction "17_17") (pintype "passive"))
      (node (ref "U1") (pin "18") (pinfunction "GPIO14/RTC_GPIO14/TOUCH14/ADC2_CH3/FSPIWP/FSPIDQS/SUBSPIWP_18") (pintype "passive"))
    )
    (net (code "37") (name "/GPIO15") (class "Default")
      (node (ref "J1") (pin "18") (pinfunction "18_18") (pintype "passive"))
      (node (ref "U1") (pin "19") (pinfunction "GPIO15/RTC_GPIO15/U0RTS/ADC2_CH4/XTAL_32K_P_19") (pintype "passive"))
    )
    (net (code "38") (name "/GPIO16") (class "Default")
      (node (ref "J1") (pin "19") (pinfunction "19_19") (pintype "passive"))
      (node (ref "U1") (pin "20") (pinfunction "GPIO16/RTC_GPIO16/U0CTS/ADC2_CH5/XTAL_32K_N_20") (pintype "passive"))
    )
    (net (code "39") (name "/GPIO17") (class "Default")
      (node (ref "J1") (pin "20") (pinfunction "20_20") (pintype "passive"))
      (node (ref "U1") (pin "21") (pinfunction "GPIO17/RTC_GPIO17/U1TXD/ADC2_CH6_21") (pintype "passive"))
    )
    (net (code "40") (name "/GPIO18") (class "Default")
      (node (ref "J1") (pin "21") (pinfunction "21_21") (pintype "passive"))
      (node (ref "U1") (pin "22") (pinfunction "GPIO18/RTC_GPIO18/U1RXD/ADC2_CH7/CLK_OUT3_22") (pintype "passive"))
    )
    (net (code "41") (name "/GPIO21") (class "Default")
      (node (ref "J2") (pin "19") (pinfunction "19_19") (pintype "passive"))
      (node (ref "U1") (pin "25") (pinfunction "GPIO21/RTC_GPIO21_25") (pintype "passive"))
    )
    (net (code "42") (name "/GPIO26") (class "Default")
      (node (ref "J2") (pin "18") (pinfunction "18_18") (pintype "passive"))
      (node (ref "U1") (pin "26") (pinfunction "GPIO26/SPICS1_26") (pintype "passive"))
    )
    (net (code "43") (name "/GPIO33") (class "Default")
      (node (ref "J2") (pin "17") (pinfunction "17_17") (pintype "passive"))
      (node (ref "U1") (pin "28") (pinfunction "GPIO33/SPIIO4/FSPIHD/SUBSPIHD_28") (pintype "passive"))
    )
    (net (code "44") (name "/GPIO34") (class "Default")
      (node (ref "J2") (pin "16") (pinfunction "16_16") (pintype "passive"))
      (node (ref "U1") (pin "29") (pinfunction "GPIO34/SPIIO5/FSPICS0/SUBSPICS0_29") (pintype "passive"))
    )
    (net (code "45") (name "/GPIO35") (class "Default")
      (node (ref "J2") (pin "15") (pinfunction "15_15") (pintype "passive"))
      (node (ref "U1") (pin "31") (pinfunction "GPIO35/SPIIO6/FSPID/SUBSPID_31") (pintype "passive"))
    )
    (net (code "46") (name "/GPIO36") (class "Default")
      (node (ref "J2") (pin "14") (pinfunction "14_14") (pintype "passive"))
      (node (ref "U1") (pin "32") (pinfunction "GPIO36/SPIIO7/FSPICLK/SUBSPICLK_32") (pintype "passive"))
    )
    (net (code "47") (name "/GPIO37") (class "Default")
      (node (ref "J2") (pin "13") (pinfunction "13_13") (pintype "passive"))
      (node (ref "U1") (pin "33") (pinfunction "GPIO37/SPIDQS/FSPIQ/SUBSPIQ_33") (pintype "passive"))
    )
    (net (code "48") (name "/GPIO38") (class "Default")
      (node (ref "J2") (pin "12") (pinfunction "12_12") (pintype "passive"))
      (node (ref "U1") (pin "34") (pinfunction "GPIO38/FSPIWP/SUBSPIWP_34") (pintype "passive"))
    )
    (net (code "49") (name "/GPIO39") (class "Default")
      (node (ref "J2") (pin "11") (pinfunction "11_11") (pintype "passive"))
      (node (ref "U1") (pin "35") (pinfunction "MTCK/GPIO39/CLK_OUT3/SUBSPICS1_35") (pintype "passive"))
    )
    (net (code "50") (name "/GPIO40") (class "Default")
      (node (ref "J2") (pin "10") (pinfunction "10_10") (pintype "passive"))
      (node (ref "U1") (pin "36") (pinfunction "MTDO/GPIO40/CLK_OUT2_36") (pintype "passive"))
    )
    (net (code "51") (name "/GPIO41") (class "Default")
      (node (ref "J2") (pin "9") (pinfunction "9_9") (pintype "passive"))
      (node (ref "U1") (pin "37") (pinfunction "MTDI/GPIO41/CLK_OUT1_37") (pintype "passive"))
    )
    (net (code "52") (name "/GPIO42") (class "Default")
      (node (ref "J2") (pin "8") (pinfunction "8_8") (pintype "passive"))
      (node (ref "U1") (pin "38") (pinfunction "MTMS/GPIO42_38") (pintype "passive"))
    )
    (net (code "53") (name "/GPIO45") (class "Default")
      (node (ref "J2") (pin "5") (pinfunction "5_5") (pintype "passive"))
      (node (ref "U1") (pin "41") (pinfunction "GPIO45_41") (pintype "passive"))
    )
    (net (code "54") (name "/GPIO46") (class "Default")
      (node (ref "J2") (pin "4") (pinfunction "4_4") (pintype "passive"))
      (node (ref "U1") (pin "44") (pinfunction "GPIO46_44") (pintype "passive"))
    )
    (net (code "55") (name "/GPIO47") (class "Default")
      (node (ref "J2") (pin "23") (pinfunction "23_23") (pintype "passive"))
      (node (ref "U1") (pin "27") (pinfunction "GPIO47/SPICLK_P_DIFF/SUBSPICLK_P_DIFF_27") (pintype "passive"))
    )
    (net (code "56") (name "/GPIO48") (class "Default")
      (node (ref "J2") (pin "22") (pinfunction "22_22") (pintype "passive"))
      (node (ref "U1") (pin "30") (pinfunction "GPIO48/SPICLK_N_DIFF/SUBSPICLK_N_DIFF_30") (pintype "passive"))
    )
    (net (code "57") (name "/RTS_FTDI") (class "Default")
      (node (ref "Q1") (pin "2") (pinfunction "E_2") (pintype "passive"))
      (node (ref "R18") (pin "1") (pinfunction "1_1") (pintype "passive"))
      (node (ref "U2") (pin "19") (pinfunction "~{RTS}_19") (pintype "passive"))
    )
    (net (code "58") (name "/RXD_FTDI") (class "Default")
      (node (ref "R19") (pin "2") (pinfunction "2_2") (pintype "passive"))
      (node (ref "U2") (pin "1") (pinfunction "RXD_1") (pintype "passive"))
    )
    (net (code "59") (name "/TXD_FTDI") (class "Default")
      (node (ref "R20") (pin "2") (pinfunction "2_2") (pintype "passive"))
      (node (ref "U2") (pin "17") (pinfunction "TXD_17") (pintype "passive"))
    )
    (net (code "60") (name "/U0RXD") (class "Default")
      (node (ref "J2") (pin "6") (pinfunction "6_6") (pintype "passive"))
      (node (ref "R20") (pin "1") (pinfunction "1_1") (pintype "passive"))
      (node (ref "U1") (pin "40") (pinfunction "U0RXD/GPIO44/CLK_OUT2_40") (pintype "passive"))
    )
    (net (code "61") (name "/U0TXD") (class "Default")
      (node (ref "J2") (pin "7") (pinfunction "7_7") (pintype "passive"))
      (node (ref "R19") (pin "1") (pinfunction "1_1") (pintype "passive"))
      (node (ref "U1") (pin "39") (pinfunction "U0TXD/GPIO43/CLK_OUT1_39") (pintype "passive"))
    )
    (net (code "62") (name "GND") (class "Default")
      (node (ref "C1") (pin "1") (pinfunction "1_1") (pintype "passive"))
      (node (ref "C10") (pin "1") (pinfunction "1_1") (pintype "passive"))
      (node (ref "C11") (pin "1") (pinfunction "1_1") (pintype "passive"))
      (node (ref "C12") (pin "1") (pinfunction "1_1") (pintype "passive"))
      (node (ref "C13") (pin "1") (pinfunction "1_1") (pintype "passive"))
      (node (ref "C14") (pin "1") (pinfunction "1_1") (pintype "passive"))
      (node (ref "C15") (pin "1") (pinfunction "1_1") (pintype "passive"))
      (node (ref "C16") (pin "1") (pinfunction "1_1") (pintype "passive"))
      (node (ref "C17") (pin "1") (pinfunction "1_1") (pintype "passive"))
      (node (ref "C2") (pin "1") (pinfunction "1_1") (pintype "passive"))
      (node (ref "C3") (pin "1") (pinfunction "1_1") (pintype "passive"))
      (node (ref "C4") (pin "1") (pinfunction "1_1") (pintype "passive"))
      (node (ref "C5") (pin "1") (pinfunction "1_1") (pintype "passive"))
      (node (ref "C6") (pin "1") (pinfunction "1_1") (pintype "passive"))
      (node (ref "C7") (pin "1") (pinfunction "1_1") (pintype "passive"))
      (node (ref "C8") (pin "1") (pinfunction "1_1") (pintype "passive"))
      (node (ref "C9") (pin "1") (pinfunction "1_1") (pintype "passive"))
      (node (ref "D1") (pin "1") (pinfunction "1_1") (pintype "passive"))
      (node (ref "D2") (pin "1") (pinfunction "1_1") (pintype "passive"))
      (node (ref "D3") (pin "1") (pinfunction "1_1") (pintype "passive"))
      (node (ref "D4") (pin "1") (pinfunction "1_1") (pintype "passive"))
      (node (ref "D6") (pin "1") (pinfunction "1_1") (pintype "passive"))
      (node (ref "D7") (pin "1") (pinfunction "1_1") (pintype "passive"))
      (node (ref "D8") (pin "1") (pinfunction "1_1") (pintype "passive"))
      (node (ref "J1") (pin "1") (pinfunction "1_1") (pintype "passive"))
      (node (ref "J1") (pin "23") (pinfunction "23_23") (pintype "passive"))
      (node (ref "J2") (pin "2") (pinfunction "2_2") (pintype "passive"))
      (node (ref "J2") (pin "24") (pinfunction "24_24") (pintype "passive"))
      (node (ref "J3") (pin "A1B12") (pinfunction "GND_A1B12_A1B12") (pintype "passive"))
      (node (ref "J3") (pin "B1A12") (pinfunction "GND_B1A12_B1A12") (pintype "passive"))
      (node (ref "J3") (pin "S1") (pinfunction "SHIELD_1_S1") (pintype "passive"))
      (node (ref "J3") (pin "S2") (pinfunction "SHIELD_2_S2") (pintype "passive"))
      (node (ref "J3") (pin "S3") (pinfunction "SHIELD_3_S3") (pintype "passive"))
      (node (ref "J3") (pin "S4") (pinfunction "SHIELD_4_S4") (pintype "passive"))
      (node (ref "J4") (pin "A1B12") (pinfunction "GND_A1B12_A1B12") (pintype "passive"))
      (node (ref "J4") (pin "B1A12") (pinfunction "GND_B1A12_B1A12") (pintype "passive"))
      (node (ref "J4") (pin "S1") (pinfunction "SHIELD_1_S1") (pintype "passive"))
      (node (ref "J4") (pin "S2") (pinfunction "SHIELD_2_S2") (pintype "passive"))
      (node (ref "J4") (pin "S3") (pinfunction "SHIELD_3_S3") (pintype "passive"))
      (node (ref "J4") (pin "S4") (pinfunction "SHIELD_4_S4") (pintype "passive"))
      (node (ref "R11") (pin "1") (pinfunction "1_1") (pintype "passive"))
      (node (ref "R12") (pin "1") (pinfunction "1_1") (pintype "passive"))
      (node (ref "R13") (pin "2") (pinfunction "2_2") (pintype "passive"))
      (node (ref "R14") (pin "1") (pinfunction "1_1") (pintype "passive"))
      (node (ref "R15") (pin "1") (pinfunction "1_1") (pintype "passive"))
      (node (ref "R9") (pin "2") (pinfunction "2_2") (pintype "passive"))
      (node (ref "SW1") (pin "3") (pinfunction "3_3") (pintype "passive"))
      (node (ref "SW1") (pin "4") (pinfunction "4_4") (pintype "passive"))
      (node (ref "SW2") (pin "3") (pinfunction "3_3") (pintype "passive"))
      (node (ref "SW2") (pin "4") (pinfunction "4_4") (pintype "passive"))
      (node (ref "U1") (pin "1") (pinfunction "GND_01_1") (pintype "passive"))
      (node (ref "U1") (pin "2") (pinfunction "GND_02_2") (pintype "passive"))
      (node (ref "U1") (pin "42") (pinfunction "GND_42") (pintype "passive"))
      (node (ref "U1") (pin "43") (pinfunction "GND_43") (pintype "passive"))
      (node (ref "U1") (pin "46") (pinfunction "GND_46_46") (pintype "passive"))
      (node (ref "U1") (pin "47") (pinfunction "GND_47_47") (pintype "passive"))
      (node (ref "U1") (pin "48") (pinfunction "GND_48_48") (pintype "passive"))
      (node (ref "U1") (pin "49") (pinfunction "GND_49_49") (pintype "passive"))
      (node (ref "U1") (pin "50") (pinfunction "GND_50_50") (pintype "passive"))
      (node (ref "U1") (pin "51") (pinfunction "GND_51_51") (pintype "passive"))
      (node (ref "U1") (pin "52") (pinfunction "GND_52_52") (pintype "passive"))
      (node (ref "U1") (pin "53") (pinfunction "GND_53_53") (pintype "passive"))
      (node (ref "U1") (pin "54") (pinfunction "GND_54_54") (pintype "passive"))
      (node (ref "U1") (pin "55") (pinfunction "GND_55_55") (pintype "passive"))
      (node (ref "U1") (pin "56") (pinfunction "GND_56_56") (pintype "passive"))
      (node (ref "U1") (pin "57") (pinfunction "GND_57_57") (pintype "passive"))
      (node (ref "U1") (pin "58") (pinfunction "GND_58_58") (pintype "passive"))
      (node (ref "U1") (pin "59") (pinfunction "GND_59_59") (pintype "passive"))
      (node (ref "U1") (pin "60") (pinfunction "GND_60_60") (pintype "passive"))
      (node (ref "U1") (pin "61") (pinfunction "GND_61_61") (pintype "passive"))
      (node (ref "U1") (pin "62") (pinfunction "GND_62_62") (pintype "passive"))
      (node (ref "U1") (pin "63") (pinfunction "GND_63_63") (pintype "passive"))
      (node (ref "U1") (pin "64") (pinfunction "GND_64_64") (pintype "passive"))
      (node (ref "U1") (pin "65") (pinfunction "GND_65_65") (pintype "passive"))
      (node (ref "U1") (pin "66") (pinfunction "GND_66_66") (pintype "passive"))
      (node (ref "U1") (pin "67") (pinfunction "GND_67_67") (pintype "passive"))
      (node (ref "U1") (pin "68") (pinfunction "GND_68_68") (pintype "passive"))
      (node (ref "U1") (pin "69") (pinfunction "GND_69_69") (pintype "passive"))
      (node (ref "U1") (pin "70") (pinfunction "GND_70_70") (pintype "passive"))
      (node (ref "U1") (pin "71") (pinfunction "GND_71_71") (pintype "passive"))
      (node (ref "U1") (pin "72") (pinfunction "GND_72_72") (pintype "passive"))
      (node (ref "U1") (pin "73") (pinfunction "GND_73_73") (pintype "passive"))
      (node (ref "U2") (pin "13") (pinfunction "GND_13") (pintype "passive"))
      (node (ref "U2") (pin "21") (pinfunction "GND_21") (pintype "passive"))
      (node (ref "U2") (pin "3") (pinfunction "GND_3") (pintype "passive"))
      (node (ref "U3") (pin "2") (pinfunction "GND_2") (pintype "power_in"))
      (node (ref "U3") (pin "4") (pinfunction "GND_4") (pintype "power_in"))
    )
    (net (code "63") (name "Net-(D4-Pad2)") (class "Default")
      (node (ref "D4") (pin "2") (pinfunction "2_2") (pintype "passive"))
      (node (ref "R3") (pin "1") (pinfunction "1_1") (pintype "passive"))
    )
    (net (code "64") (name "Net-(D5-Pad2)") (class "Default")
      (node (ref "D5") (pin "2") (pinfunction "2_2") (pintype "passive"))
      (node (ref "R4") (pin "1") (pinfunction "1_1") (pintype "passive"))
    )
    (net (code "65") (name "Net-(J3-CC1)") (class "Default")
      (node (ref "J3") (pin "A5") (pinfunction "CC1_A5") (pintype "passive"))
      (node (ref "R12") (pin "2") (pinfunction "2_2") (pintype "passive"))
    )
    (net (code "66") (name "Net-(J3-CC2)") (class "Default")
      (node (ref "J3") (pin "B5") (pinfunction "CC2_B5") (pintype "passive"))
      (node (ref "R11") (pin "2") (pinfunction "2_2") (pintype "passive"))
    )
    (net (code "67") (name "Net-(J4-CC1)") (class "Default")
      (node (ref "J4") (pin "A5") (pinfunction "CC1_A5") (pintype "passive"))
      (node (ref "R15") (pin "2") (pinfunction "2_2") (pintype "passive"))
    )
    (net (code "68") (name "Net-(J4-CC2)") (class "Default")
      (node (ref "J4") (pin "B5") (pinfunction "CC2_B5") (pintype "passive"))
      (node (ref "R14") (pin "2") (pinfunction "2_2") (pintype "passive"))
    )
    (net (code "69") (name "Net-(Q1-B)") (class "Default")
      (node (ref "Q1") (pin "1") (pinfunction "B_1") (pintype "passive"))
      (node (ref "R16") (pin "2") (pinfunction "2_2") (pintype "passive"))
    )
    (net (code "70") (name "Net-(Q2-B)") (class "Default")
      (node (ref "Q2") (pin "1") (pinfunction "B_1") (pintype "passive"))
      (node (ref "R18") (pin "2") (pinfunction "2_2") (pintype "passive"))
    )
    (net (code "71") (name "Net-(U2-CBUS0)") (class "Default")
      (node (ref "R9") (pin "1") (pinfunction "1_1") (pintype "passive"))
      (node (ref "U2") (pin "15") (pinfunction "CBUS0_15") (pintype "passive"))
    )
    (net (code "72") (name "Net-(U2-CBUS3)") (class "Default")
      (node (ref "R10") (pin "1") (pinfunction "1_1") (pintype "passive"))
      (node (ref "R13") (pin "1") (pinfunction "1_1") (pintype "passive"))
      (node (ref "U2") (pin "16") (pinfunction "CBUS3_16") (pintype "passive"))
    )
    (net (code "73") (name "Net-(U2-VCC)") (class "Default")
      (node (ref "C1") (pin "2") (pinfunction "2_2") (pintype "passive"))
      (node (ref "C2") (pin "2") (pinfunction "2_2") (pintype "passive"))
      (node (ref "R1") (pin "2") (pinfunction "2_2") (pintype "passive"))
      (node (ref "R2") (pin "2") (pinfunction "2_2") (pintype "passive"))
      (node (ref "U2") (pin "12") (pinfunction "VCC_12") (pintype "passive"))
    )
    (net (code "74") (name "unconnected-(J1-Pad24)") (class "Default")
      (node (ref "J1") (pin "24") (pinfunction "24_24") (pintype "passive+no_connect"))
    )
    (net (code "75") (name "unconnected-(J3-SBU1-PadA8)") (class "Default")
      (node (ref "J3") (pin "A8") (pinfunction "SBU1_A8") (pintype "passive+no_connect"))
    )
    (net (code "76") (name "unconnected-(J3-SBU2-PadB8)") (class "Default")
      (node (ref "J3") (pin "B8") (pinfunction "SBU2_B8") (pintype "passive+no_connect"))
    )
    (net (code "77") (name "unconnected-(J4-SBU1-PadA8)") (class "Default")
      (node (ref "J4") (pin "A8") (pinfunction "SBU1_A8") (pintype "passive+no_connect"))
    )
    (net (code "78") (name "unconnected-(J4-SBU2-PadB8)") (class "Default")
      (node (ref "J4") (pin "B8") (pinfunction "SBU2_B8") (pintype "passive+no_connect"))
    )
    (net (code "79") (name "unconnected-(U2-CBUS1-Pad14)") (class "Default")
      (node (ref "U2") (pin "14") (pinfunction "CBUS1_14") (pintype "passive+no_connect"))
    )
    (net (code "80") (name "unconnected-(U2-CBUS2-Pad7)") (class "Default")
      (node (ref "U2") (pin "7") (pinfunction "CBUS2_7") (pintype "passive+no_connect"))
    )
    (net (code "81") (name "unconnected-(U2-~{CTS}-Pad6)") (class "Default")
      (node (ref "U2") (pin "6") (pinfunction "~{CTS}_6") (pintype "passive+no_connect"))
    )
    (net (code "82") (name "unconnected-(U2-~{DCD}-Pad5)") (class "Default")
      (node (ref "U2") (pin "5") (pinfunction "~{DCD}_5") (pintype "passive+no_connect"))
    )
    (net (code "83") (name "unconnected-(U2-~{DSR}-Pad4)") (class "Default")
      (node (ref "U2") (pin "4") (pinfunction "~{DSR}_4") (pintype "passive+no_connect"))
    )
    (net (code "84") (name "unconnected-(U2-~{RI}-Pad2)") (class "Default")
      (node (ref "U2") (pin "2") (pinfunction "~{RI}_2") (pintype "passive+no_connect"))
    )
  )
)
